# Dual_PMT_Controller_-_Light_Interlock.net
KiCad netlist of a schematic drawn in Altium Designer
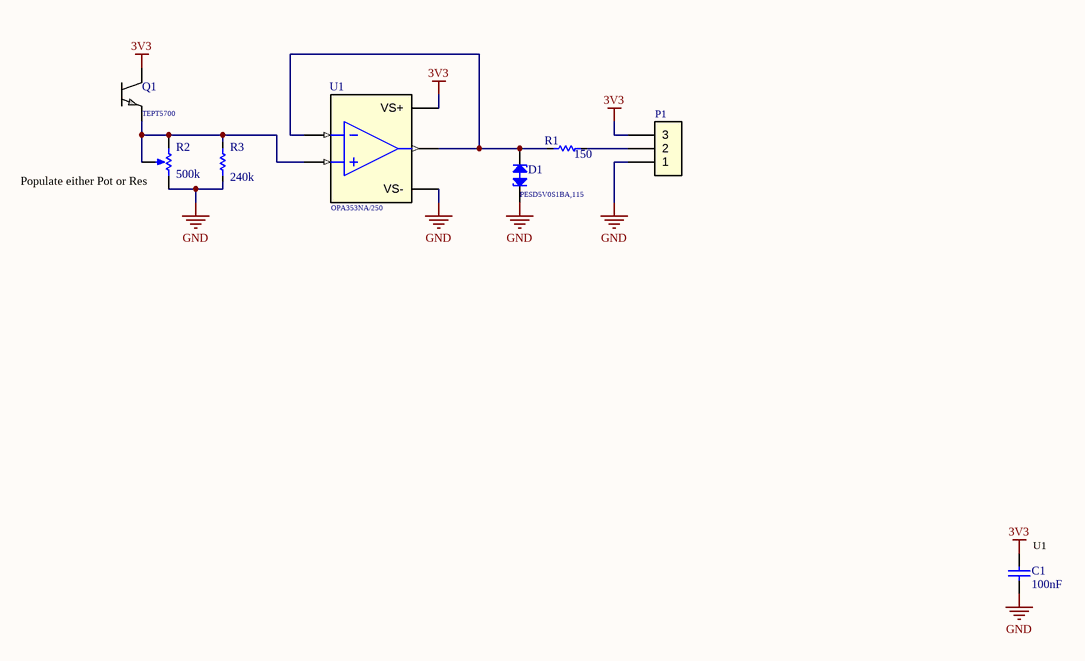
[diagram p0: Dual PMT Controller - Light Interlock.SchDoc]

(export (version "E")
  (design (tool "Eeschema 10.0.6"))
  (components
    (comp (ref "C1")
      (value "100nF")
      (footprint "FP-GRM188-0_1-e0_2_0_5-IPC_B")
      (description "0.1µF ±10% 100V Ceramic Capacitor X7R 0603 (1608 Metric)")
      (fields (field (name "TOLERANCE") "10%") (field (name "VOLTAGE") "100V"))
      (libsource (lib "Sainsbury Wellcome Centre") (part "Cap"))
    )
    (comp (ref "D1")
      (value "PESD5V0S1BA,115")
      (footprint "FP-SOD323-CA-IPC_B")
      (description "Trans Voltage Suppressor Diode, 130W, 5V V(RWM), Bidirectional, 1 Element, Silicon")
      (fields (field (name "PARTNUMBER") "PESD5V0S1BA,115"))
      (libsource (lib "Sainsbury Wellcome Centre") (part "BI-ESD"))
    )
    (comp (ref "P1")
      (value "Header-103")
      (footprint "Header-103")
      (description "0.1\" spaced holes to solder wires into")
      (libsource (lib "Sainsbury Wellcome Centre") (part "Header 3"))
    )
    (comp (ref "Q1")
      (value "TEPT5700")
      (footprint "LED_TEPT5700_VIS")
      (description "Ambient Light Sensor Phototransistor Chip Silicon 570nm 2-Pin T-1 3/4")
      (libsource (lib "Sainsbury Wellcome Centre") (part "Phototransistor C1E2"))
    )
    (comp (ref "R1")
      (value "150")
      (footprint "FP-CPF0603-IPC_B")
      (description "Surface Mount Resistor 150 Ohm 1/16 W 0.1% 0603 (1608 Metric)")
      (fields (field (name "TOLERANCE") "0.1%") (field (name "Comment") "R0603-150R-1/16W-0.1%"))
      (libsource (lib "Sainsbury Wellcome Centre") (part "Res"))
    )
    (comp (ref "R2")
      (value "500k")
      (footprint "SM-42TAxxx_NDC")
      (description "Trimmer, Cermet, 0.25W, 500k ohm, 300V, 10% +/-Tol, 100ppm/Cel, 11 Turn(s), 1918")
      (fields (field (name "PARTNUMBER") "SM-42TA504") (field (name "TOLERANCE") "10%"))
      (libsource (lib "Sainsbury Wellcome Centre") (part "Pot-W2"))
    )
    (comp (ref "R3")
      (value "240k")
      (footprint "FP-CPF0603-IPC_B")
      (description "Surface Mount Resistor 240k Ohm 1/16 W 0.1% 0603 (1608 Metric)")
      (fields (field (name "TOLERANCE") "0.1%") (field (name "Comment") "R0603-240k-1/16W-0.1%"))
      (libsource (lib "Sainsbury Wellcome Centre") (part "Res"))
    )
    (comp (ref "U1")
      (value "OPA353NA/250")
      (footprint "DBV0005A_N")
      (description "Operational Amplifier, 1 Func, 8000uV Offset-Max, CMOS, PDSO5")
      (fields (field (name "PARTNUMBER") "OPA353NA/250"))
      (libsource (lib "Sainsbury Wellcome Centre") (part "TI-AMP-S3-2-DBV5_A"))
    )
  )
  (nets
    (net (code "1") (name "3V3") (class "Default")
      (node (ref "C1") (pin "2") (pinfunction "2_2") (pintype "passive"))
      (node (ref "P1") (pin "3") (pinfunction "3_3") (pintype "passive"))
      (node (ref "Q1") (pin "1") (pinfunction "C_1") (pintype "passive"))
      (node (ref "U1") (pin "5") (pinfunction "VS+_5") (pintype "power_in"))
    )
    (net (code "2") (name "GND") (class "Default")
      (node (ref "C1") (pin "1") (pinfunction "1_1") (pintype "passive"))
      (node (ref "D1") (pin "1") (pinfunction "K1_1") (pintype "passive"))
      (node (ref "P1") (pin "1") (pinfunction "1_1") (pintype "passive"))
      (node (ref "R2") (pin "3") (pinfunction "BOT_3") (pintype "passive"))
      (node (ref "R3") (pin "1") (pinfunction "1_1") (pintype "passive"))
      (node (ref "U1") (pin "2") (pinfunction "VS-_2") (pintype "power_in"))
    )
    (net (code "3") (name "Net-(D1-K2)") (class "Default")
      (node (ref "D1") (pin "2") (pinfunction "K2_2") (pintype "passive"))
      (node (ref "R1") (pin "1") (pinfunction "1_1") (pintype "passive"))
      (node (ref "U1") (pin "1") (pinfunction "OUT_1") (pintype "output"))
      (node (ref "U1") (pin "4") (pinfunction "IN-_4") (pintype "input"))
    )
    (net (code "4") (name "Net-(P1-Pad2)") (class "Default")
      (node (ref "P1") (pin "2") (pinfunction "2_2") (pintype "passive"))
      (node (ref "R1") (pin "2") (pinfunction "2_2") (pintype "passive"))
    )
    (net (code "5") (name "Net-(Q1-E)") (class "Default")
      (node (ref "Q1") (pin "2") (pinfunction "E_2") (pintype "passive"))
      (node (ref "R2") (pin "1") (pinfunction "TOP_1") (pintype "passive"))
      (node (ref "R2") (pin "2") (pinfunction "TAP_2") (pintype "passive"))
      (node (ref "R3") (pin "2") (pinfunction "2_2") (pintype "passive"))
      (node (ref "U1") (pin "3") (pinfunction "IN+_3") (pintype "input"))
    )
  )
)
